# W25Qxx-SpiFlash.net
KiCad netlist of a schematic drawn in Altium Designer
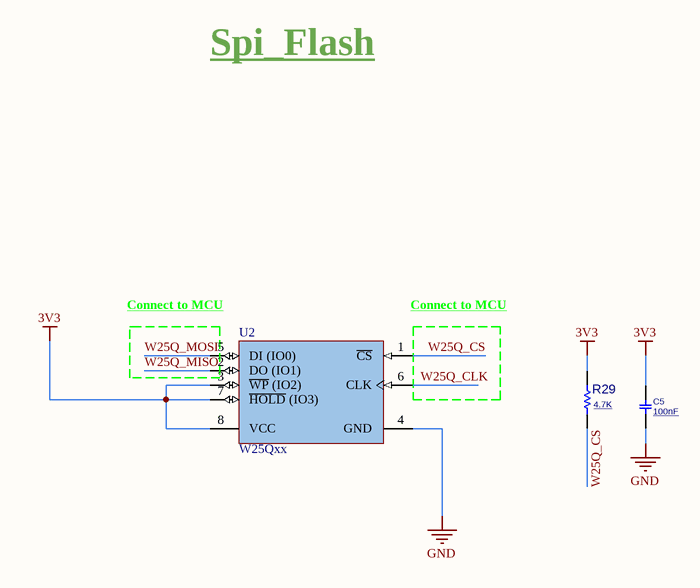
[diagram p0: W25Qxx-SpiFlash.SchDoc]

(export (version "E")
  (design (tool "Eeschema 10.0.6"))
  (components
    (comp (ref "C5")
      (value "100nF")
      (footprint "C0603")
      (description "CAP, MLCC, -F, -V, MATERIAL, -%, 0201")
      (fields (field (name "MANF_P#") "MANF_PART#"))
      (libsource (lib "passive_smd") (part "CAP_SMD_MLCC_0603"))
    )
    (comp (ref "R29")
      (value "4.7K")
      (footprint "R0603")
      (description "RESISTOR, SMD")
      (libsource (lib "passive_smd") (part "RES_SMD"))
    )
    (comp (ref "U2")
      (value "W25Qxx")
      (footprint "WINB-SOIC-8_M")
      (fields (field (name "MANUFACTURER") "Winbond"))
      (libsource (lib "w25qxx") (part "W25Qxx"))
    )
  )
  (nets
    (net (code "1") (name "/W25Q_CLK") (class "Default")
      (node (ref "U2") (pin "6") (pinfunction "CLK_6") (pintype "input"))
    )
    (net (code "2") (name "/W25Q_CS") (class "Default")
      (node (ref "R29") (pin "1") (pinfunction "1_1") (pintype "passive"))
      (node (ref "U2") (pin "1") (pinfunction "~{CS}_1") (pintype "input"))
    )
    (net (code "3") (name "/W25Q_MISO") (class "Default")
      (node (ref "U2") (pin "2") (pinfunction "DO_(IO1)_2") (pintype "bidirectional"))
    )
    (net (code "4") (name "/W25Q_MOSI") (class "Default")
      (node (ref "U2") (pin "5") (pinfunction "DI_(IO0)_5") (pintype "bidirectional"))
    )
    (net (code "5") (name "3V3") (class "Default")
      (node (ref "C5") (pin "2") (pinfunction "2_2") (pintype "passive"))
      (node (ref "R29") (pin "2") (pinfunction "2_2") (pintype "passive"))
      (node (ref "U2") (pin "3") (pinfunction "~{WP}_(IO2)_3") (pintype "bidirectional"))
      (node (ref "U2") (pin "7") (pinfunction "~{HOLD}_(IO3)_7") (pintype "bidirectional"))
      (node (ref "U2") (pin "8") (pinfunction "VCC_8") (pintype "power_in"))
    )
    (net (code "6") (name "GND") (class "Default")
      (node (ref "C5") (pin "1") (pinfunction "1_1") (pintype "passive"))
      (node (ref "U2") (pin "4") (pinfunction "GND_4") (pintype "power_in"))
    )
  )
)
